# v1_1.net
KiCad netlist of a schematic drawn in EAGLE
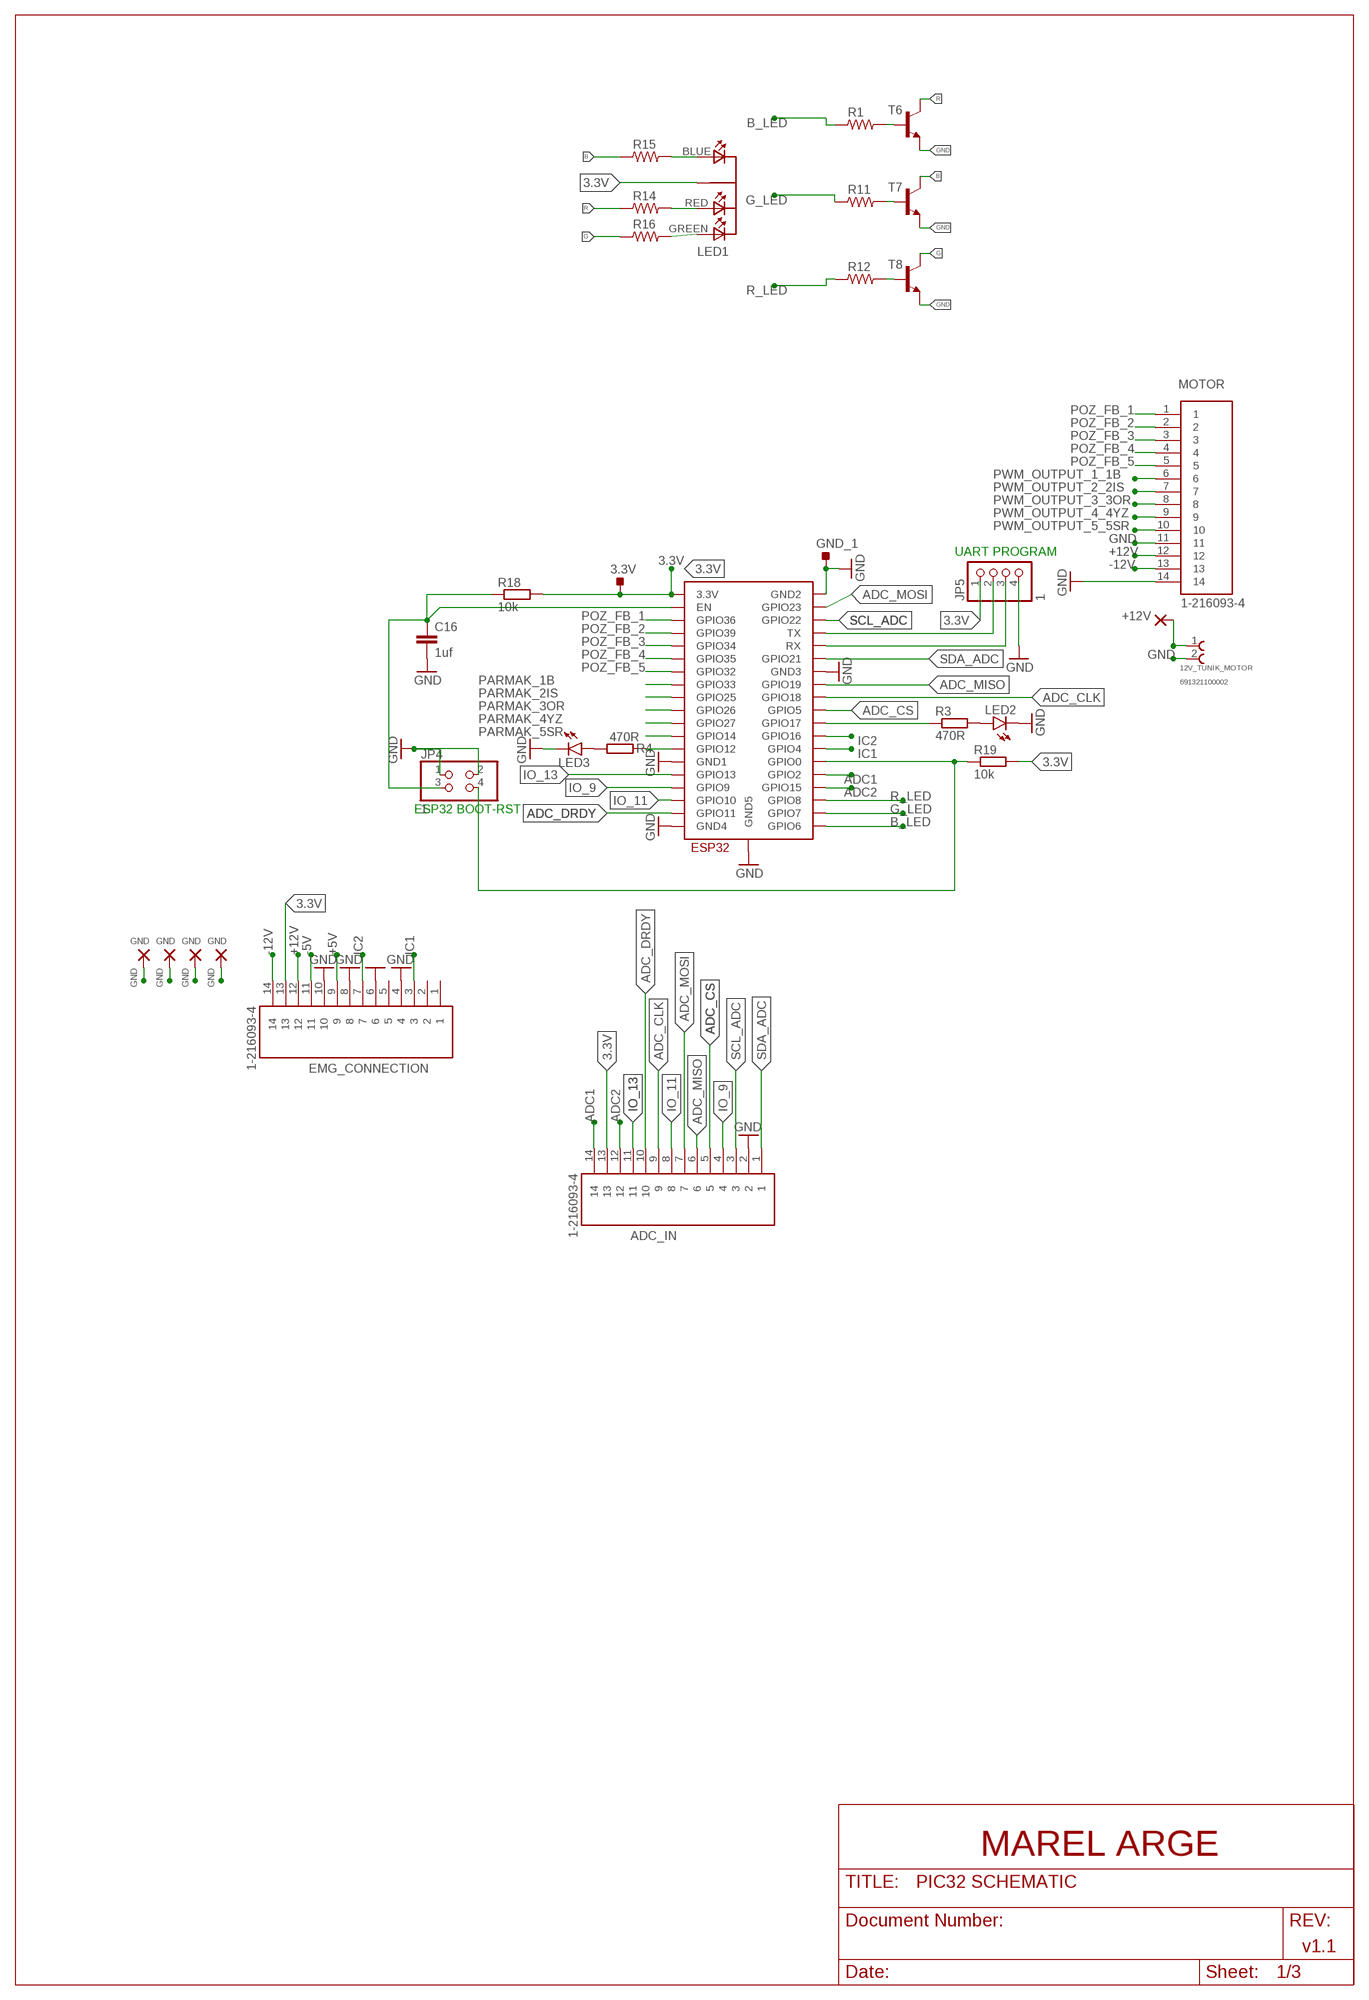
[diagram p0: schematic, sheet 1]
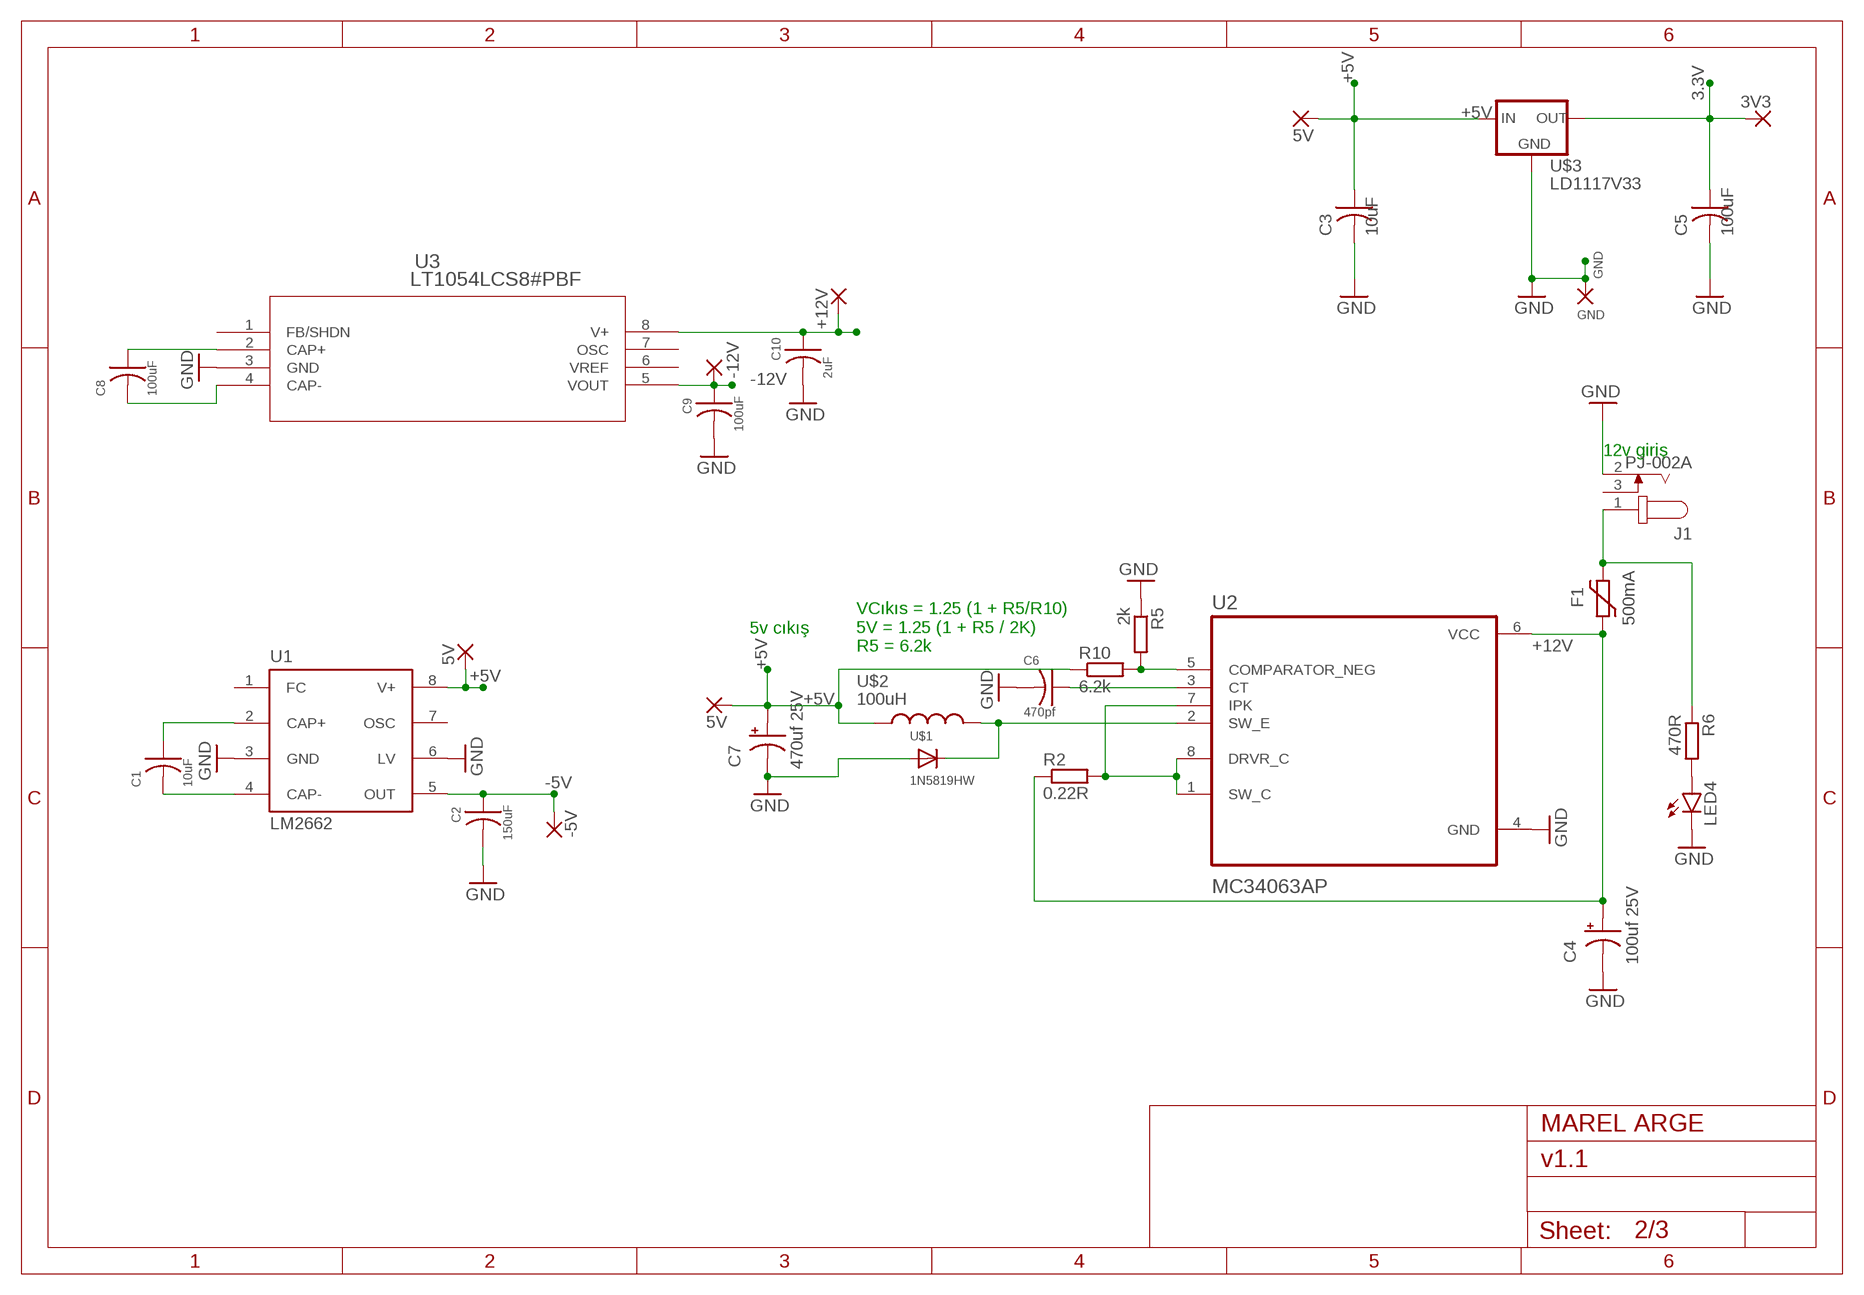
[diagram p1: schematic, sheet 2]
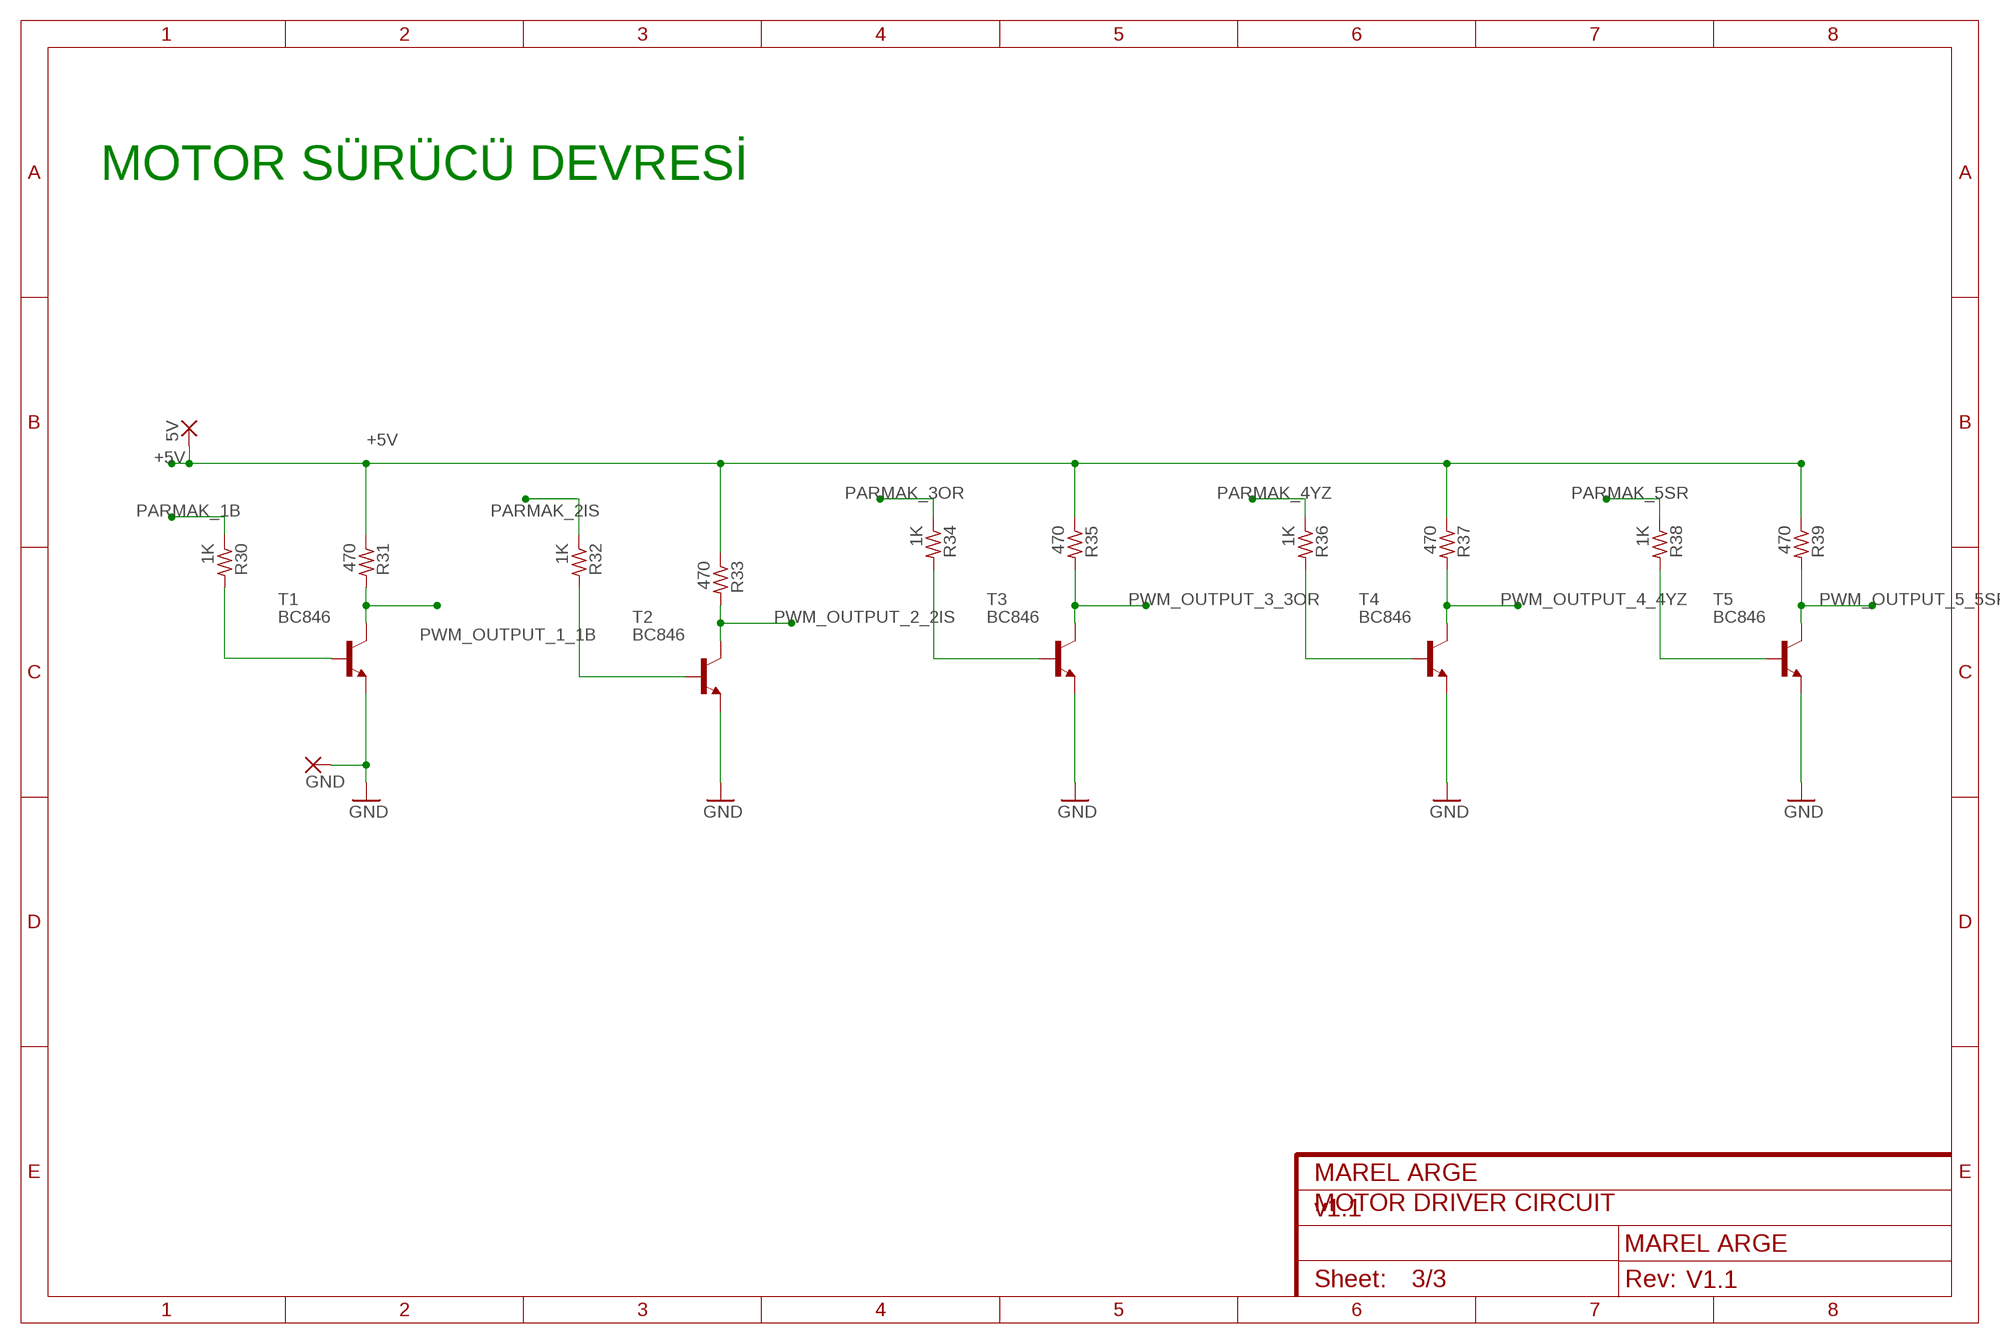
[diagram p2: schematic, sheet 3]

(export (version "E")
  (design (tool "Eeschema 10.0.6"))
  (components
    (comp (ref "GND_")
      (value "GND")
      (footprint "eagle-import:2,54_0,8")
      (libsource (lib "eagle-import") (part "2,54/0,8"))
    )
    (comp (ref "R30")
      (value "1K")
      (footprint "eagle-import:M0805")
      (libsource (lib "eagle-import") (part "R-US_M0805"))
    )
    (comp (ref "R31")
      (value "470")
      (footprint "eagle-import:M0805")
      (libsource (lib "eagle-import") (part "R-US_M0805"))
    )
    (comp (ref "R32")
      (value "1K")
      (footprint "eagle-import:M0805")
      (libsource (lib "eagle-import") (part "R-US_M0805"))
    )
    (comp (ref "R33")
      (value "470")
      (footprint "eagle-import:M0805")
      (libsource (lib "eagle-import") (part "R-US_M0805"))
    )
    (comp (ref "R34")
      (value "1K")
      (footprint "eagle-import:M0805")
      (libsource (lib "eagle-import") (part "R-US_M0805"))
    )
    (comp (ref "R35")
      (value "470")
      (footprint "eagle-import:M0805")
      (libsource (lib "eagle-import") (part "R-US_M0805"))
    )
    (comp (ref "R36")
      (value "1K")
      (footprint "eagle-import:M0805")
      (libsource (lib "eagle-import") (part "R-US_M0805"))
    )
    (comp (ref "R37")
      (value "470")
      (footprint "eagle-import:M0805")
      (libsource (lib "eagle-import") (part "R-US_M0805"))
    )
    (comp (ref "R38")
      (value "1K")
      (footprint "eagle-import:M0805")
      (libsource (lib "eagle-import") (part "R-US_M0805"))
    )
    (comp (ref "R39")
      (value "470")
      (footprint "eagle-import:M0805")
      (libsource (lib "eagle-import") (part "R-US_M0805"))
    )
    (comp (ref "T1")
      (value "BC846")
      (footprint "eagle-import:SOT23")
      (libsource (lib "eagle-import") (part "BC846"))
    )
    (comp (ref "T2")
      (value "BC846")
      (footprint "eagle-import:SOT23")
      (libsource (lib "eagle-import") (part "BC846"))
    )
    (comp (ref "T3")
      (value "BC846")
      (footprint "eagle-import:SOT23")
      (libsource (lib "eagle-import") (part "BC846"))
    )
    (comp (ref "T4")
      (value "BC846")
      (footprint "eagle-import:SOT23")
      (libsource (lib "eagle-import") (part "BC846"))
    )
    (comp (ref "T5")
      (value "BC846")
      (footprint "eagle-import:SOT23")
      (libsource (lib "eagle-import") (part "BC846"))
    )
    (comp (ref "_5VOLT")
      (value "5V")
      (footprint "eagle-import:2,54_0,8")
      (libsource (lib "eagle-import") (part "2,54/0,8"))
    )
    (comp (ref "3.3V")
      (value "TESTPOINT_TPS-SMD-10SN")
      (footprint "eagle-import:TESTPOINT_SMD-10SN")
      (libsource (lib "eagle-import") (part "TESTPOINT_TPS-SMD-10SN"))
    )
    (comp (ref "12VOLT")
      (value "12V")
      (footprint "eagle-import:2,54_0,8")
      (libsource (lib "eagle-import") (part "2,54/0,8"))
    )
    (comp (ref "12V_TUNİK_MOTOR")
      (value "691321100002")
      (footprint "eagle-import:691321100002")
      (fields (field (name "MF") "Wurth Electronics"))
      (libsource (lib "eagle-import") (part "691321100002"))
    )
    (comp (ref "ADC_IN")
      (value "1-216093-4")
      (footprint "eagle-import:TE_1-216093-4")
      (fields (field (name "MF") "TE Connectivity"))
      (libsource (lib "eagle-import") (part "1-216093-4"))
    )
    (comp (ref "C16")
      (value "1uf")
      (footprint "eagle-import:C0805")
      (libsource (lib "eagle-import") (part "C-EUC0805"))
    )
    (comp (ref "EMG_CONNECTION")
      (value "1-216093-4")
      (footprint "eagle-import:TE_1-216093-4")
      (fields (field (name "MF") "TE Connectivity"))
      (libsource (lib "eagle-import") (part "1-216093-4"))
    )
    (comp (ref "GND18")
      (value "GND")
      (footprint "eagle-import:2,54_0,8")
      (libsource (lib "eagle-import") (part "2,54/0,8"))
    )
    (comp (ref "GND19")
      (value "GND")
      (footprint "eagle-import:2,54_0,8")
      (libsource (lib "eagle-import") (part "2,54/0,8"))
    )
    (comp (ref "GND20")
      (value "GND")
      (footprint "eagle-import:2,54_0,8")
      (libsource (lib "eagle-import") (part "2,54/0,8"))
    )
    (comp (ref "GND21")
      (value "GND")
      (footprint "eagle-import:2,54_0,8")
      (libsource (lib "eagle-import") (part "2,54/0,8"))
    )
    (comp (ref "GND_1")
      (value "TESTPOINT_TPS-SMD-10SN")
      (footprint "eagle-import:TESTPOINT_SMD-10SN")
      (libsource (lib "eagle-import") (part "TESTPOINT_TPS-SMD-10SN"))
    )
    (comp (ref "JP4")
      (value "1")
      (footprint "eagle-import:2X02")
      (libsource (lib "eagle-import") (part "PINHD-2X2"))
    )
    (comp (ref "JP5")
      (value "1")
      (footprint "eagle-import:1X04")
      (libsource (lib "eagle-import") (part "PINHD-1X4"))
    )
    (comp (ref "LED1")
      (value "LED-DIP-3")
      (footprint "eagle-import:DIP-4")
      (libsource (lib "eagle-import") (part "LED-DIP-3"))
    )
    (comp (ref "LED2")
      (value "LED5MM")
      (footprint "eagle-import:LED5MM")
      (libsource (lib "eagle-import") (part "LED5MM"))
    )
    (comp (ref "LED3")
      (value "LED5MM")
      (footprint "eagle-import:LED5MM")
      (libsource (lib "eagle-import") (part "LED5MM"))
    )
    (comp (ref "MOTOR")
      (value "1-216093-4")
      (footprint "eagle-import:TE_1-216093-4")
      (fields (field (name "MF") "TE Connectivity"))
      (libsource (lib "eagle-import") (part "1-216093-4"))
    )
    (comp (ref "R1")
      (value "100R")
      (footprint "eagle-import:RC-MASTER-SMD_R0603MP")
      (fields (field (name "SPICEPREFIX") "R"))
      (libsource (lib "eagle-import") (part "RC-MASTER-SMD_RESISTOR0603MP"))
    )
    (comp (ref "R3")
      (value "470R")
      (footprint "eagle-import:R0603")
      (libsource (lib "eagle-import") (part "R-EU_R0603"))
    )
    (comp (ref "R4")
      (value "470R")
      (footprint "eagle-import:R0603")
      (libsource (lib "eagle-import") (part "R-EU_R0603"))
    )
    (comp (ref "R11")
      (value "100R")
      (footprint "eagle-import:RC-MASTER-SMD_R0603MP")
      (fields (field (name "SPICEPREFIX") "R"))
      (libsource (lib "eagle-import") (part "RC-MASTER-SMD_RESISTOR0603MP"))
    )
    (comp (ref "R12")
      (value "100R")
      (footprint "eagle-import:RC-MASTER-SMD_R0603MP")
      (fields (field (name "SPICEPREFIX") "R"))
      (libsource (lib "eagle-import") (part "RC-MASTER-SMD_RESISTOR0603MP"))
    )
    (comp (ref "R14")
      (value "100R")
      (footprint "eagle-import:RC-MASTER-SMD_R0603MP")
      (fields (field (name "SPICEPREFIX") "R"))
      (libsource (lib "eagle-import") (part "RC-MASTER-SMD_RESISTOR0603MP"))
    )
    (comp (ref "R15")
      (value "100R")
      (footprint "eagle-import:RC-MASTER-SMD_R0603MP")
      (fields (field (name "SPICEPREFIX") "R"))
      (libsource (lib "eagle-import") (part "RC-MASTER-SMD_RESISTOR0603MP"))
    )
    (comp (ref "R16")
      (value "100R")
      (footprint "eagle-import:RC-MASTER-SMD_R0603MP")
      (fields (field (name "SPICEPREFIX") "R"))
      (libsource (lib "eagle-import") (part "RC-MASTER-SMD_RESISTOR0603MP"))
    )
    (comp (ref "R18")
      (value "10k")
      (footprint "eagle-import:R0603")
      (libsource (lib "eagle-import") (part "R-EU_R0603"))
    )
    (comp (ref "R19")
      (value "10k")
      (footprint "eagle-import:R0603")
      (libsource (lib "eagle-import") (part "R-EU_R0603"))
    )
    (comp (ref "T6")
      (value "TRANSISTORBC846BLT1SOT23-BEC")
      (footprint "eagle-import:SOT23-BEC")
      (libsource (lib "eagle-import") (part "TRANSISTORSOT23-BECBC846BLT1"))
    )
    (comp (ref "T7")
      (value "TRANSISTORBC846BLT1SOT23-BEC")
      (footprint "eagle-import:SOT23-BEC")
      (libsource (lib "eagle-import") (part "TRANSISTORSOT23-BECBC846BLT1"))
    )
    (comp (ref "T8")
      (value "TRANSISTORBC846BLT1SOT23-BEC")
      (footprint "eagle-import:SOT23-BEC")
      (libsource (lib "eagle-import") (part "TRANSISTORSOT23-BECBC846BLT1"))
    )
    (comp (ref "U$7")
      (value "ESP32-WROOM")
      (footprint "eagle-import:ESP32-WROOM")
      (libsource (lib "eagle-import") (part "ESP32-WROOM"))
    )
    (comp (ref "+5V")
      (value "5V")
      (footprint "eagle-import:2,54_0,8")
      (libsource (lib "eagle-import") (part "2,54/0,8"))
    )
    (comp (ref "+12V")
      (value "+12V")
      (footprint "eagle-import:2,54_0,8")
      (libsource (lib "eagle-import") (part "2,54/0,8"))
    )
    (comp (ref "-5V")
      (value "-5V")
      (footprint "eagle-import:2,54_0,8")
      (libsource (lib "eagle-import") (part "2,54/0,8"))
    )
    (comp (ref "-12V")
      (value "-12V")
      (footprint "eagle-import:2,54_0,8")
      (libsource (lib "eagle-import") (part "2,54/0,8"))
    )
    (comp (ref "3V3_1")
      (value "3V3")
      (footprint "eagle-import:2,54_0,8")
      (libsource (lib "eagle-import") (part "2,54/0,8"))
    )
    (comp (ref "5V")
      (value "5V")
      (footprint "eagle-import:2,54_0,8")
      (libsource (lib "eagle-import") (part "2,54/0,8"))
    )
    (comp (ref "5V1")
      (value "5V")
      (footprint "eagle-import:2,54_0,8")
      (libsource (lib "eagle-import") (part "2,54/0,8"))
    )
    (comp (ref "C1")
      (value "10uF")
      (footprint "eagle-import:C1206")
      (libsource (lib "eagle-import") (part "C-USC1206"))
    )
    (comp (ref "C2")
      (value "150uF")
      (footprint "eagle-import:C1206")
      (libsource (lib "eagle-import") (part "C-USC1206"))
    )
    (comp (ref "C3")
      (value "10uF")
      (footprint "eagle-import:C1206")
      (libsource (lib "eagle-import") (part "C-USC1206"))
    )
    (comp (ref "C4")
      (value "100uf 25V")
      (footprint "eagle-import:X")
      (fields
        (field (name "MANUFACTURER") "Kemet")
        (field (name "PART_NUMBER") "T491X107K025AT")
        (field (name "TOLERANCE") "10%")
      )
      (libsource (lib "eagle-import") (part "T491?X107K025AT"))
    )
    (comp (ref "C5")
      (value "100uF")
      (footprint "eagle-import:C1206")
      (libsource (lib "eagle-import") (part "C-USC1206"))
    )
    (comp (ref "C6")
      (value "470pf")
      (footprint "eagle-import:C1206")
      (libsource (lib "eagle-import") (part "C-USC1206"))
    )
    (comp (ref "C7")
      (value "470uf 25V")
      (footprint "eagle-import:X")
      (fields
        (field (name "MANUFACTURER") "Kemet")
        (field (name "PART_NUMBER") "T491X107K025AT")
        (field (name "TOLERANCE") "10%")
      )
      (libsource (lib "eagle-import") (part "T491?X107K025AT"))
    )
    (comp (ref "C8")
      (value "100uF")
      (footprint "eagle-import:C1206")
      (libsource (lib "eagle-import") (part "C-USC1206"))
    )
    (comp (ref "C9")
      (value "100uF")
      (footprint "eagle-import:C1206")
      (libsource (lib "eagle-import") (part "C-USC1206"))
    )
    (comp (ref "C10")
      (value "2uF")
      (footprint "eagle-import:C1206")
      (libsource (lib "eagle-import") (part "C-USC1206"))
    )
    (comp (ref "F1")
      (value "500mA")
      (footprint "eagle-import:1206L")
      (libsource (lib "eagle-import") (part "1206L"))
    )
    (comp (ref "GND13")
      (value "GND")
      (footprint "eagle-import:2,54_0,8")
      (libsource (lib "eagle-import") (part "2,54/0,8"))
    )
    (comp (ref "J1")
      (value "PJ-002A")
      (footprint "eagle-import:CUI_PJ-002A")
      (fields (field (name "MF") "CUI Devices"))
      (libsource (lib "eagle-import") (part "PJ-002A"))
    )
    (comp (ref "LED4")
      (value "LED5MM")
      (footprint "eagle-import:LED5MM")
      (libsource (lib "eagle-import") (part "LED5MM"))
    )
    (comp (ref "R2")
      (value "0.22R")
      (footprint "eagle-import:R2512")
      (libsource (lib "eagle-import") (part "R-EU_R2512"))
    )
    (comp (ref "R5")
      (value "2k")
      (footprint "eagle-import:R0805")
      (libsource (lib "eagle-import") (part "R-EU_R0805"))
    )
    (comp (ref "R6")
      (value "470R")
      (footprint "eagle-import:R0603")
      (libsource (lib "eagle-import") (part "R-EU_R0603"))
    )
    (comp (ref "R10")
      (value "6.2k")
      (footprint "eagle-import:R0805")
      (libsource (lib "eagle-import") (part "R-EU_R0805"))
    )
    (comp (ref "U$1")
      (value "1N5819HW")
      (footprint "eagle-import:SOD-123-EDITED")
      (libsource (lib "eagle-import") (part "1N5819HW"))
    )
    (comp (ref "U$2")
      (value "100uH")
      (footprint "eagle-import:L7070")
      (libsource (lib "eagle-import") (part "INDUCTOR7070"))
    )
    (comp (ref "U$3")
      (value "LD1117V33")
      (footprint "eagle-import:LD1117V33")
      (libsource (lib "eagle-import") (part "LD1117V33"))
    )
    (comp (ref "U1")
      (value "LM2662")
      (footprint "eagle-import:SO08")
      (libsource (lib "eagle-import") (part "LM2662"))
    )
    (comp (ref "U2")
      (value "MC34063AP")
      (footprint "eagle-import:DIP794W45P254L959H508Q8")
      (fields (field (name "MF") "Texas Instruments"))
      (libsource (lib "eagle-import") (part "MC34063AP"))
    )
    (comp (ref "U3")
      (value "LT1054LCS8#PBF")
      (footprint "eagle-import:SO-8_S")
      (fields (field (name "MF") "Analog Devices"))
      (libsource (lib "eagle-import") (part "LT1054LCS8#PBF"))
    )
  )
  (nets
    (net (code "1") (name "+5V") (class "Default")
      (node (ref "+5V") (pin "1") (pinfunction "P_1") (pintype "passive"))
      (node (ref "5V") (pin "1") (pinfunction "P_1") (pintype "passive"))
      (node (ref "5V1") (pin "1") (pinfunction "P_1") (pintype "passive"))
      (node (ref "C3") (pin "1") (pinfunction "1_1") (pintype "passive"))
      (node (ref "C7") (pin "A") (pinfunction "A_A") (pintype "passive"))
      (node (ref "EMG_CONNECTION") (pin "9") (pinfunction "9_9") (pintype "passive"))
      (node (ref "R10") (pin "1") (pinfunction "1_1") (pintype "passive"))
      (node (ref "R31") (pin "1") (pinfunction "1_1") (pintype "passive"))
      (node (ref "R33") (pin "1") (pinfunction "1_1") (pintype "passive"))
      (node (ref "R35") (pin "1") (pinfunction "1_1") (pintype "passive"))
      (node (ref "R37") (pin "1") (pinfunction "1_1") (pintype "passive"))
      (node (ref "R39") (pin "1") (pinfunction "1_1") (pintype "passive"))
      (node (ref "U$2") (pin "1") (pinfunction "1_1") (pintype "passive"))
      (node (ref "U$3") (pin "IN") (pinfunction "IN_IN") (pintype "input"))
      (node (ref "U1") (pin "8") (pinfunction "V+_8") (pintype "bidirectional"))
      (node (ref "_5VOLT") (pin "1") (pinfunction "P_1") (pintype "passive"))
    )
    (net (code "2") (name "+12V") (class "Default")
      (node (ref "+12V") (pin "1") (pinfunction "P_1") (pintype "passive"))
      (node (ref "12VOLT") (pin "1") (pinfunction "P_1") (pintype "passive"))
      (node (ref "12V_TUNİK_MOTOR") (pin "1") (pinfunction "1_1") (pintype "passive"))
      (node (ref "C10") (pin "1") (pinfunction "1_1") (pintype "passive"))
      (node (ref "C4") (pin "A") (pinfunction "A_A") (pintype "passive"))
      (node (ref "EMG_CONNECTION") (pin "12") (pinfunction "12_12") (pintype "passive"))
      (node (ref "F1") (pin "P$1") (pinfunction "1_P$1") (pintype "passive"))
      (node (ref "MOTOR") (pin "12") (pinfunction "12_12") (pintype "passive"))
      (node (ref "R2") (pin "1") (pinfunction "1_1") (pintype "passive"))
      (node (ref "U2") (pin "6") (pinfunction "VCC_6") (pintype "power_in"))
      (node (ref "U3") (pin "8") (pinfunction "V+_8") (pintype "power_in"))
    )
    (net (code "3") (name "-5V") (class "Default")
      (node (ref "-5V") (pin "1") (pinfunction "P_1") (pintype "passive"))
      (node (ref "C2") (pin "1") (pinfunction "1_1") (pintype "passive"))
      (node (ref "EMG_CONNECTION") (pin "11") (pinfunction "11_11") (pintype "passive"))
      (node (ref "U1") (pin "5") (pinfunction "OUT_5") (pintype "bidirectional"))
    )
    (net (code "4") (name "-12V") (class "Default")
      (node (ref "-12V") (pin "1") (pinfunction "P_1") (pintype "passive"))
      (node (ref "C9") (pin "1") (pinfunction "1_1") (pintype "passive"))
      (node (ref "EMG_CONNECTION") (pin "14") (pinfunction "14_14") (pintype "passive"))
      (node (ref "MOTOR") (pin "13") (pinfunction "13_13") (pintype "passive"))
      (node (ref "U3") (pin "5") (pinfunction "VOUT_5") (pintype "output"))
    )
    (net (code "5") (name "3.3V") (class "Default")
      (node (ref "3.3V") (pin "TP") (pinfunction "TP_TP") (pintype "passive"))
      (node (ref "3V3_1") (pin "1") (pinfunction "P_1") (pintype "passive"))
      (node (ref "ADC_IN") (pin "13") (pinfunction "13_13") (pintype "passive"))
      (node (ref "C5") (pin "1") (pinfunction "1_1") (pintype "passive"))
      (node (ref "EMG_CONNECTION") (pin "13") (pinfunction "13_13") (pintype "passive"))
      (node (ref "JP5") (pin "1") (pinfunction "1_1") (pintype "passive"))
      (node (ref "LED1") (pin "COMMON_CATHODE") (pinfunction "COM-CATHODE_COMMON_CATHODE") (pintype "passive"))
      (node (ref "R18") (pin "2") (pinfunction "2_2") (pintype "passive"))
      (node (ref "R19") (pin "2") (pinfunction "2_2") (pintype "passive"))
      (node (ref "U$3") (pin "OUT") (pinfunction "OUT_OUT") (pintype "output"))
      (node (ref "U$7") (pin "3V3") (pinfunction "3.3V_3V3") (pintype "bidirectional"))
    )
    (net (code "6") (name "ADC1") (class "Default")
      (node (ref "ADC_IN") (pin "14") (pinfunction "14_14") (pintype "passive"))
      (node (ref "U$7") (pin "IO2") (pinfunction "GPIO2_IO2") (pintype "bidirectional"))
    )
    (net (code "7") (name "ADC2") (class "Default")
      (node (ref "ADC_IN") (pin "12") (pinfunction "12_12") (pintype "passive"))
      (node (ref "U$7") (pin "IO15") (pinfunction "GPIO15_IO15") (pintype "bidirectional"))
    )
    (net (code "8") (name "ADC_CLK") (class "Default")
      (node (ref "ADC_IN") (pin "9") (pinfunction "9_9") (pintype "passive"))
      (node (ref "U$7") (pin "IO18") (pinfunction "GPIO18_IO18") (pintype "bidirectional"))
    )
    (net (code "9") (name "ADC_CS") (class "Default")
      (node (ref "ADC_IN") (pin "5") (pinfunction "5_5") (pintype "passive"))
      (node (ref "U$7") (pin "IO5") (pinfunction "GPIO5_IO5") (pintype "bidirectional"))
    )
    (net (code "10") (name "ADC_DRDY") (class "Default")
      (node (ref "ADC_IN") (pin "10") (pinfunction "10_10") (pintype "passive"))
      (node (ref "U$7") (pin "CMD") (pinfunction "GPIO11_CMD") (pintype "bidirectional"))
    )
    (net (code "11") (name "ADC_MISO") (class "Default")
      (node (ref "ADC_IN") (pin "6") (pinfunction "6_6") (pintype "passive"))
      (node (ref "U$7") (pin "IO19") (pinfunction "GPIO19_IO19") (pintype "bidirectional"))
    )
    (net (code "12") (name "ADC_MOSI") (class "Default")
      (node (ref "ADC_IN") (pin "7") (pinfunction "7_7") (pintype "passive"))
      (node (ref "U$7") (pin "IO23") (pinfunction "GPIO23_IO23") (pintype "bidirectional"))
    )
    (net (code "13") (name "B") (class "Default")
      (node (ref "R14") (pin "1") (pinfunction "1_1") (pintype "passive"))
      (node (ref "T7") (pin "C") (pinfunction "C_C") (pintype "passive"))
    )
    (net (code "14") (name "B_LED") (class "Default")
      (node (ref "R1") (pin "1") (pinfunction "1_1") (pintype "passive"))
      (node (ref "U$7") (pin "CLK") (pinfunction "GPIO6_CLK") (pintype "bidirectional"))
    )
    (net (code "15") (name "G") (class "Default")
      (node (ref "R16") (pin "1") (pinfunction "1_1") (pintype "passive"))
      (node (ref "T8") (pin "C") (pinfunction "C_C") (pintype "passive"))
    )
    (net (code "16") (name "GND") (class "Default")
      (node (ref "12V_TUNİK_MOTOR") (pin "2") (pinfunction "2_2") (pintype "passive"))
      (node (ref "ADC_IN") (pin "2") (pinfunction "2_2") (pintype "passive"))
      (node (ref "C10") (pin "2") (pinfunction "2_2") (pintype "passive"))
      (node (ref "C16") (pin "2") (pinfunction "2_2") (pintype "passive"))
      (node (ref "C2") (pin "2") (pinfunction "2_2") (pintype "passive"))
      (node (ref "C3") (pin "2") (pinfunction "2_2") (pintype "passive"))
      (node (ref "C4") (pin "C") (pinfunction "C_C") (pintype "passive"))
      (node (ref "C5") (pin "2") (pinfunction "2_2") (pintype "passive"))
      (node (ref "C6") (pin "2") (pinfunction "2_2") (pintype "passive"))
      (node (ref "C7") (pin "C") (pinfunction "C_C") (pintype "passive"))
      (node (ref "C9") (pin "2") (pinfunction "2_2") (pintype "passive"))
      (node (ref "EMG_CONNECTION") (pin "10") (pinfunction "10_10") (pintype "passive"))
      (node (ref "EMG_CONNECTION") (pin "4") (pinfunction "4_4") (pintype "passive"))
      (node (ref "EMG_CONNECTION") (pin "6") (pinfunction "6_6") (pintype "passive"))
      (node (ref "EMG_CONNECTION") (pin "8") (pinfunction "8_8") (pintype "passive"))
      (node (ref "GND13") (pin "1") (pinfunction "P_1") (pintype "passive"))
      (node (ref "GND18") (pin "1") (pinfunction "P_1") (pintype "passive"))
      (node (ref "GND19") (pin "1") (pinfunction "P_1") (pintype "passive"))
      (node (ref "GND20") (pin "1") (pinfunction "P_1") (pintype "passive"))
      (node (ref "GND21") (pin "1") (pinfunction "P_1") (pintype "passive"))
      (node (ref "GND_") (pin "1") (pinfunction "P_1") (pintype "passive"))
      (node (ref "GND_1") (pin "TP") (pinfunction "TP_TP") (pintype "passive"))
      (node (ref "J1") (pin "2") (pinfunction "2_2") (pintype "passive"))
      (node (ref "JP4") (pin "1") (pinfunction "1_1") (pintype "passive"))
      (node (ref "JP4") (pin "2") (pinfunction "2_2") (pintype "passive"))
      (node (ref "JP5") (pin "4") (pinfunction "4_4") (pintype "passive"))
      (node (ref "LED2") (pin "K") (pinfunction "C_K") (pintype "passive"))
      (node (ref "LED3") (pin "K") (pinfunction "C_K") (pintype "passive"))
      (node (ref "LED4") (pin "K") (pinfunction "C_K") (pintype "passive"))
      (node (ref "MOTOR") (pin "11") (pinfunction "11_11") (pintype "passive"))
      (node (ref "MOTOR") (pin "14") (pinfunction "14_14") (pintype "passive"))
      (node (ref "R5") (pin "1") (pinfunction "1_1") (pintype "passive"))
      (node (ref "T1") (pin "2") (pinfunction "E_2") (pintype "passive"))
      (node (ref "T2") (pin "2") (pinfunction "E_2") (pintype "passive"))
      (node (ref "T3") (pin "2") (pinfunction "E_2") (pintype "passive"))
      (node (ref "T4") (pin "2") (pinfunction "E_2") (pintype "passive"))
      (node (ref "T5") (pin "2") (pinfunction "E_2") (pintype "passive"))
      (node (ref "T6") (pin "E") (pinfunction "E_E") (pintype "passive"))
      (node (ref "T7") (pin "E") (pinfunction "E_E") (pintype "passive"))
      (node (ref "T8") (pin "E") (pinfunction "E_E") (pintype "passive"))
      (node (ref "U$1") (pin "A") (pinfunction "A_A") (pintype "passive"))
      (node (ref "U$3") (pin "GND") (pinfunction "GND_GND") (pintype "input"))
      (node (ref "U$7") (pin "GND1") (pinfunction "GND1_GND1") (pintype "bidirectional"))
      (node (ref "U$7") (pin "GND2") (pinfunction "GND2_GND2") (pintype "bidirectional"))
      (node (ref "U$7") (pin "GND3") (pinfunction "GND3_GND3") (pintype "bidirectional"))
      (node (ref "U$7") (pin "GND4") (pinfunction "GND4_GND4") (pintype "bidirectional"))
      (node (ref "U$7") (pin "GND5") (pinfunction "GND5_GND5") (pintype "bidirectional"))
      (node (ref "U1") (pin "3") (pinfunction "GND_3") (pintype "bidirectional"))
      (node (ref "U1") (pin "6") (pinfunction "LV_6") (pintype "bidirectional"))
      (node (ref "U2") (pin "4") (pinfunction "GND_4") (pintype "power_in"))
      (node (ref "U3") (pin "3") (pinfunction "GND_3") (pintype "power_in"))
    )
    (net (code "17") (name "G_LED") (class "Default")
      (node (ref "R11") (pin "1") (pinfunction "1_1") (pintype "passive"))
      (node (ref "U$7") (pin "SD0") (pinfunction "GPIO7_SD0") (pintype "bidirectional"))
    )
    (net (code "18") (name "IC1") (class "Default")
      (node (ref "EMG_CONNECTION") (pin "3") (pinfunction "3_3") (pintype "passive"))
      (node (ref "U$7") (pin "IO4") (pinfunction "GPIO4_IO4") (pintype "bidirectional"))
    )
    (net (code "19") (name "IC2") (class "Default")
      (node (ref "EMG_CONNECTION") (pin "7") (pinfunction "7_7") (pintype "passive"))
      (node (ref "U$7") (pin "IO16") (pinfunction "GPIO16_IO16") (pintype "bidirectional"))
    )
    (net (code "20") (name "IO_9") (class "Default")
      (node (ref "ADC_IN") (pin "4") (pinfunction "4_4") (pintype "passive"))
      (node (ref "U$7") (pin "SD2") (pinfunction "GPIO9_SD2") (pintype "bidirectional"))
    )
    (net (code "21") (name "IO_11") (class "Default")
      (node (ref "ADC_IN") (pin "8") (pinfunction "8_8") (pintype "passive"))
      (node (ref "U$7") (pin "SD3") (pinfunction "GPIO10_SD3") (pintype "bidirectional"))
    )
    (net (code "22") (name "IO_13") (class "Default")
      (node (ref "ADC_IN") (pin "11") (pinfunction "11_11") (pintype "passive"))
      (node (ref "U$7") (pin "IO13") (pinfunction "GPIO13_IO13") (pintype "bidirectional"))
    )
    (net (code "23") (name "Net-(C16-Pad1)") (class "Default")
      (node (ref "C16") (pin "1") (pinfunction "1_1") (pintype "passive"))
      (node (ref "JP4") (pin "3") (pinfunction "3_3") (pintype "passive"))
      (node (ref "R18") (pin "1") (pinfunction "1_1") (pintype "passive"))
      (node (ref "U$7") (pin "EN") (pinfunction "EN_EN") (pintype "bidirectional"))
    )
    (net (code "24") (name "Net-(F1-2)") (class "Default")
      (node (ref "F1") (pin "P$2") (pinfunction "2_P$2") (pintype "passive"))
      (node (ref "J1") (pin "1") (pinfunction "1_1") (pintype "passive"))
      (node (ref "R6") (pin "1") (pinfunction "1_1") (pintype "passive"))
    )
    (net (code "25") (name "Net-(JP5-Pad2)") (class "Default")
      (node (ref "JP5") (pin "2") (pinfunction "2_2") (pintype "passive"))
      (node (ref "U$7") (pin "TX") (pinfunction "TX_TX") (pintype "bidirectional"))
    )
    (net (code "26") (name "Net-(JP5-Pad3)") (class "Default")
      (node (ref "JP5") (pin "3") (pinfunction "3_3") (pintype "passive"))
      (node (ref "U$7") (pin "RX") (pinfunction "RX_RX") (pintype "bidirectional"))
    )
    (net (code "27") (name "Net-(LED1-PadBLUE)") (class "Default")
      (node (ref "LED1") (pin "BLUE") (pinfunction "BLUE_BLUE") (pintype "passive"))
      (node (ref "R15") (pin "2") (pinfunction "2_2") (pintype "passive"))
    )
    (net (code "28") (name "Net-(LED1-PadGREEN)") (class "Default")
      (node (ref "LED1") (pin "GREEN") (pinfunction "GREEN_GREEN") (pintype "passive"))
      (node (ref "R16") (pin "2") (pinfunction "2_2") (pintype "passive"))
    )
    (net (code "29") (name "Net-(LED1-PadRED)") (class "Default")
      (node (ref "LED1") (pin "RED") (pinfunction "RED_RED") (pintype "passive"))
      (node (ref "R14") (pin "2") (pinfunction "2_2") (pintype "passive"))
    )
    (net (code "30") (name "Net-(LED2-PadA)") (class "Default")
      (node (ref "LED2") (pin "A") (pinfunction "A_A") (pintype "passive"))
      (node (ref "R3") (pin "2") (pinfunction "2_2") (pintype "passive"))
    )
    (net (code "31") (name "Net-(LED3-PadA)") (class "Default")
      (node (ref "LED3") (pin "A") (pinfunction "A_A") (pintype "passive"))
      (node (ref "R4") (pin "2") (pinfunction "2_2") (pintype "passive"))
    )
    (net (code "32") (name "Net-(LED4-PadA)") (class "Default")
      (node (ref "LED4") (pin "A") (pinfunction "A_A") (pintype "passive"))
      (node (ref "R6") (pin "2") (pinfunction "2_2") (pintype "passive"))
    )
    (net (code "33") (name "Net-(R1-Pad2)") (class "Default")
      (node (ref "R1") (pin "2") (pinfunction "2_2") (pintype "passive"))
      (node (ref "T6") (pin "B") (pinfunction "B_B") (pintype "passive"))
    )
    (net (code "34") (name "Net-(R11-Pad2)") (class "Default")
      (node (ref "R11") (pin "2") (pinfunction "2_2") (pintype "passive"))
      (node (ref "T7") (pin "B") (pinfunction "B_B") (pintype "passive"))
    )
    (net (code "35") (name "Net-(R12-Pad2)") (class "Default")
      (node (ref "R12") (pin "2") (pinfunction "2_2") (pintype "passive"))
      (node (ref "T8") (pin "B") (pinfunction "B_B") (pintype "passive"))
    )
    (net (code "36") (name "Net-(T1-B)") (class "Default")
      (node (ref "R30") (pin "2") (pinfunction "2_2") (pintype "passive"))
      (node (ref "T1") (pin "1") (pinfunction "B_1") (pintype "passive"))
    )
    (net (code "37") (name "Net-(T2-B)") (class "Default")
      (node (ref "R32") (pin "2") (pinfunction "2_2") (pintype "passive"))
      (node (ref "T2") (pin "1") (pinfunction "B_1") (pintype "passive"))
    )
    (net (code "38") (name "Net-(T3-B)") (class "Default")
      (node (ref "R34") (pin "2") (pinfunction "2_2") (pintype "passive"))
      (node (ref "T3") (pin "1") (pinfunction "B_1") (pintype "passive"))
    )
    (net (code "39") (name "Net-(T4-B)") (class "Default")
      (node (ref "R36") (pin "2") (pinfunction "2_2") (pintype "passive"))
      (node (ref "T4") (pin "1") (pinfunction "B_1") (pintype "passive"))
    )
    (net (code "40") (name "Net-(T5-B)") (class "Default")
      (node (ref "R38") (pin "2") (pinfunction "2_2") (pintype "passive"))
      (node (ref "T5") (pin "1") (pinfunction "B_1") (pintype "passive"))
    )
    (net (code "41") (name "Net-(U$7-GPIO0)") (class "Default")
      (node (ref "JP4") (pin "4") (pinfunction "4_4") (pintype "passive"))
      (node (ref "R19") (pin "1") (pinfunction "1_1") (pintype "passive"))
      (node (ref "U$7") (pin "IO0") (pinfunction "GPIO0_IO0") (pintype "bidirectional"))
    )
    (net (code "42") (name "Net-(U$7-GPIO12)") (class "Default")
      (node (ref "R4") (pin "1") (pinfunction "1_1") (pintype "passive"))
      (node (ref "U$7") (pin "IO12") (pinfunction "GPIO12_IO12") (pintype "bidirectional"))
    )
    (net (code "43") (name "Net-(U$7-GPIO17)") (class "Default")
      (node (ref "R3") (pin "1") (pinfunction "1_1") (pintype "passive"))
      (node (ref "U$7") (pin "IO17") (pinfunction "GPIO17_IO17") (pintype "bidirectional"))
    )
    (net (code "44") (name "Net-(U1-CAP+)") (class "Default")
      (node (ref "C1") (pin "1") (pinfunction "1_1") (pintype "passive"))
      (node (ref "U1") (pin "2") (pinfunction "CAP+_2") (pintype "bidirectional"))
    )
    (net (code "45") (name "Net-(U1-CAP-)") (class "Default")
      (node (ref "C1") (pin "2") (pinfunction "2_2") (pintype "passive"))
      (node (ref "U1") (pin "4") (pinfunction "CAP-_4") (pintype "bidirectional"))
    )
    (net (code "46") (name "Net-(U2-COMPARATOR_NEG)") (class "Default")
      (node (ref "R10") (pin "2") (pinfunction "2_2") (pintype "passive"))
      (node (ref "R5") (pin "2") (pinfunction "2_2") (pintype "passive"))
      (node (ref "U2") (pin "5") (pinfunction "COMPARATOR_NEG_5") (pintype "input"))
    )
    (net (code "47") (name "Net-(U2-CT)") (class "Default")
      (node (ref "C6") (pin "1") (pinfunction "1_1") (pintype "passive"))
      (node (ref "U2") (pin "3") (pinfunction "CT_3") (pintype "input"))
    )
    (net (code "48") (name "Net-(U2-DRVR_C)") (class "Default")
      (node (ref "R2") (pin "2") (pinfunction "2_2") (pintype "passive"))
      (node (ref "U2") (pin "1") (pinfunction "SW_C_1") (pintype "bidirectional"))
      (node (ref "U2") (pin "7") (pinfunction "IPK_7") (pintype "input"))
      (node (ref "U2") (pin "8") (pinfunction "DRVR_C_8") (pintype "bidirectional"))
    )
    (net (code "49") (name "Net-(U2-SW_E)") (class "Default")
      (node (ref "U$1") (pin "C") (pinfunction "C_C") (pintype "passive"))
      (node (ref "U$2") (pin "2") (pinfunction "2_2") (pintype "passive"))
      (node (ref "U2") (pin "2") (pinfunction "SW_E_2") (pintype "input"))
    )
    (net (code "50") (name "Net-(U3-CAP+)") (class "Default")
      (node (ref "C8") (pin "1") (pinfunction "1_1") (pintype "passive"))
      (node (ref "U3") (pin "2") (pinfunction "CAP+_2") (pintype "passive"))
    )
    (net (code "51") (name "Net-(U3-CAP-)") (class "Default")
      (node (ref "C8") (pin "2") (pinfunction "2_2") (pintype "passive"))
      (node (ref "U3") (pin "4") (pinfunction "CAP-_4") (pintype "passive"))
    )
    (net (code "52") (name "PARMAK_1B") (class "Default")
      (node (ref "R30") (pin "1") (pinfunction "1_1") (pintype "passive"))
      (node (ref "U$7") (pin "IO33") (pinfunction "GPIO33_IO33") (pintype "bidirectional"))
    )
    (net (code "53") (name "PARMAK_2IS") (class "Default")
      (node (ref "R32") (pin "1") (pinfunction "1_1") (pintype "passive"))
      (node (ref "U$7") (pin "IO25") (pinfunction "GPIO25_IO25") (pintype "bidirectional"))
    )
    (net (code "54") (name "PARMAK_3OR") (class "Default")
      (node (ref "R34") (pin "1") (pinfunction "1_1") (pintype "passive"))
      (node (ref "U$7") (pin "IO26") (pinfunction "GPIO26_IO26") (pintype "bidirectional"))
    )
    (net (code "55") (name "PARMAK_4YZ") (class "Default")
      (node (ref "R36") (pin "1") (pinfunction "1_1") (pintype "passive"))
      (node (ref "U$7") (pin "IO27") (pinfunction "GPIO27_IO27") (pintype "bidirectional"))
    )
    (net (code "56") (name "PARMAK_5SR") (class "Default")
      (node (ref "R38") (pin "1") (pinfunction "1_1") (pintype "passive"))
      (node (ref "U$7") (pin "IO14") (pinfunction "GPIO14_IO14") (pintype "bidirectional"))
    )
    (net (code "57") (name "POZ_FB_1") (class "Default")
      (node (ref "MOTOR") (pin "1") (pinfunction "1_1") (pintype "passive"))
      (node (ref "U$7") (pin "SENSOR_VP") (pinfunction "GPIO36_SENSOR_VP") (pintype "bidirectional"))
    )
    (net (code "58") (name "POZ_FB_2") (class "Default")
      (node (ref "MOTOR") (pin "2") (pinfunction "2_2") (pintype "passive"))
      (node (ref "U$7") (pin "SENSOR_VN") (pinfunction "GPIO39_SENSOR_VN") (pintype "bidirectional"))
    )
    (net (code "59") (name "POZ_FB_3") (class "Default")
      (node (ref "MOTOR") (pin "3") (pinfunction "3_3") (pintype "passive"))
      (node (ref "U$7") (pin "IO34") (pinfunction "GPIO34_IO34") (pintype "bidirectional"))
    )
    (net (code "60") (name "POZ_FB_4") (class "Default")
      (node (ref "MOTOR") (pin "4") (pinfunction "4_4") (pintype "passive"))
      (node (ref "U$7") (pin "IO35") (pinfunction "GPIO35_IO35") (pintype "bidirectional"))
    )
    (net (code "61") (name "POZ_FB_5") (class "Default")
      (node (ref "MOTOR") (pin "5") (pinfunction "5_5") (pintype "passive"))
      (node (ref "U$7") (pin "IO32") (pinfunction "GPIO32_IO32") (pintype "bidirectional"))
    )
    (net (code "62") (name "PWM_OUTPUT_1_1B") (class "Default")
      (node (ref "MOTOR") (pin "6") (pinfunction "6_6") (pintype "passive"))
      (node (ref "R31") (pin "2") (pinfunction "2_2") (pintype "passive"))
      (node (ref "T1") (pin "3") (pinfunction "C_3") (pintype "passive"))
    )
    (net (code "63") (name "PWM_OUTPUT_2_2IS") (class "Default")
      (node (ref "MOTOR") (pin "7") (pinfunction "7_7") (pintype "passive"))
      (node (ref "R33") (pin "2") (pinfunction "2_2") (pintype "passive"))
      (node (ref "T2") (pin "3") (pinfunction "C_3") (pintype "passive"))
    )
    (net (code "64") (name "PWM_OUTPUT_3_3OR") (class "Default")
      (node (ref "MOTOR") (pin "8") (pinfunction "8_8") (pintype "passive"))
      (node (ref "R35") (pin "2") (pinfunction "2_2") (pintype "passive"))
      (node (ref "T3") (pin "3") (pinfunction "C_3") (pintype "passive"))
    )
    (net (code "65") (name "PWM_OUTPUT_4_4YZ") (class "Default")
      (node (ref "MOTOR") (pin "9") (pinfunction "9_9") (pintype "passive"))
      (node (ref "R37") (pin "2") (pinfunction "2_2") (pintype "passive"))
      (node (ref "T4") (pin "3") (pinfunction "C_3") (pintype "passive"))
    )
    (net (code "66") (name "PWM_OUTPUT_5_5SR") (class "Default")
      (node (ref "MOTOR") (pin "10") (pinfunction "10_10") (pintype "passive"))
      (node (ref "R39") (pin "2") (pinfunction "2_2") (pintype "passive"))
      (node (ref "T5") (pin "3") (pinfunction "C_3") (pintype "passive"))
    )
    (net (code "67") (name "R") (class "Default")
      (node (ref "R15") (pin "1") (pinfunction "1_1") (pintype "passive"))
      (node (ref "T6") (pin "C") (pinfunction "C_C") (pintype "passive"))
    )
    (net (code "68") (name "R_LED") (class "Default")
      (node (ref "R12") (pin "1") (pinfunction "1_1") (pintype "passive"))
      (node (ref "U$7") (pin "SD1") (pinfunction "GPIO8_SD1") (pintype "bidirectional"))
    )
    (net (code "69") (name "SCL_ADC") (class "Default")
      (node (ref "ADC_IN") (pin "3") (pinfunction "3_3") (pintype "passive"))
      (node (ref "U$7") (pin "IO22") (pinfunction "GPIO22_IO22") (pintype "bidirectional"))
    )
    (net (code "70") (name "SDA_ADC") (class "Default")
      (node (ref "ADC_IN") (pin "1") (pinfunction "1_1") (pintype "passive"))
      (node (ref "U$7") (pin "IO21") (pinfunction "GPIO21_IO21") (pintype "bidirectional"))
    )
    (net (code "71") (name "VREF") (class "Default")
      (node (ref "U3") (pin "6") (pinfunction "VREF_6") (pintype "power_in"))
    )
    (net (code "72") (name "unconnected-(EMG_CONNECTION-Pad1)") (class "Default")
      (node (ref "EMG_CONNECTION") (pin "1") (pinfunction "1_1") (pintype "passive"))
    )
    (net (code "73") (name "unconnected-(EMG_CONNECTION-Pad2)") (class "Default")
      (node (ref "EMG_CONNECTION") (pin "2") (pinfunction "2_2") (pintype "passive"))
    )
    (net (code "74") (name "unconnected-(EMG_CONNECTION-Pad5)") (class "Default")
      (node (ref "EMG_CONNECTION") (pin "5") (pinfunction "5_5") (pintype "passive"))
    )
    (net (code "75") (name "unconnected-(J1-Pad3)") (class "Default")
      (node (ref "J1") (pin "3") (pinfunction "3_3") (pintype "passive"))
    )
    (net (code "76") (name "unconnected-(U1-FC-Pad1)") (class "Default")
      (node (ref "U1") (pin "1") (pinfunction "FC_1") (pintype "bidirectional"))
    )
    (net (code "77") (name "unconnected-(U1-OSC-Pad7)") (class "Default")
      (node (ref "U1") (pin "7") (pinfunction "OSC_7") (pintype "bidirectional"))
    )
    (net (code "78") (name "unconnected-(U3-FB{slash}SHDN-Pad1)") (class "Default")
      (node (ref "U3") (pin "1") (pinfunction "FB/SHDN_1") (pintype "passive"))
    )
    (net (code "79") (name "unconnected-(U3-OSC-Pad7)") (class "Default")
      (node (ref "U3") (pin "7") (pinfunction "OSC_7") (pintype "passive"))
    )
  )
)
